# DM1098OAKW_Connector.net
KiCad netlist of a schematic drawn in Altium Designer
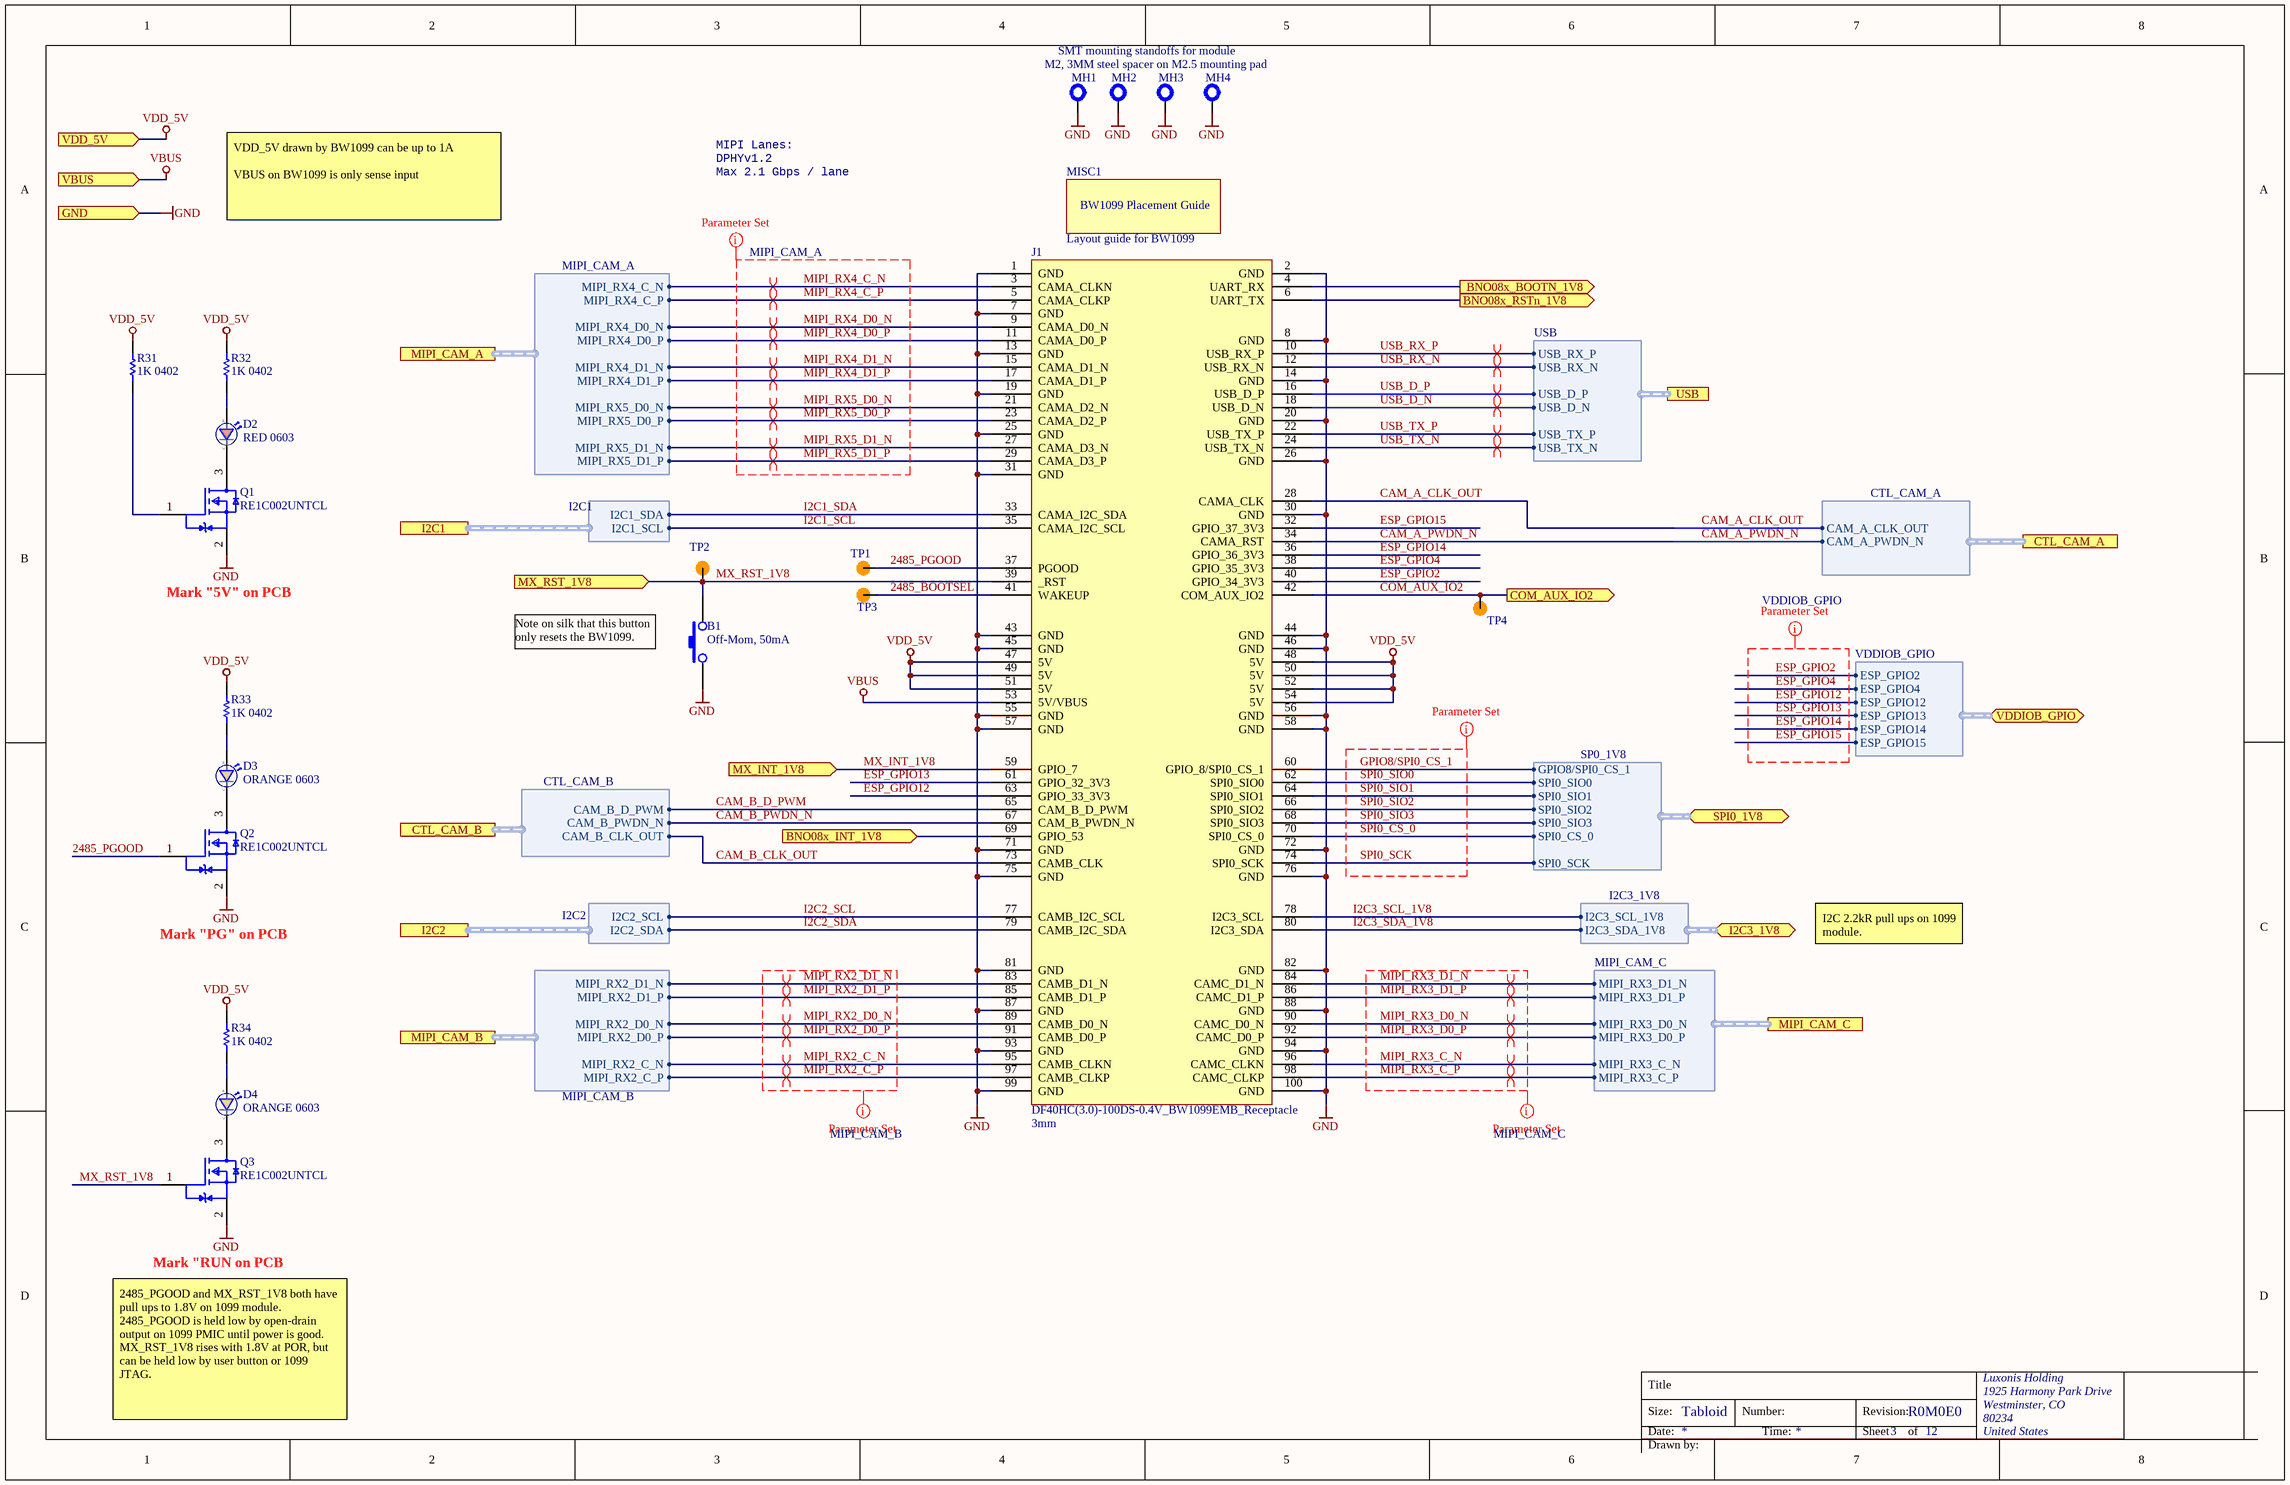
[diagram p0: DM1098OAKW_Connector.SchDoc]

(export (version "E")
  (design (tool "Eeschema 10.0.6"))
  (components
    (comp (ref "B1")
      (value "Off-Mom, 50mA")
      (footprint "LuxonisMaster:DTSM-32N-V")
      (description "SWITCH TACTILE SMT 3.5mm * 6mm , brown 160gf")
      (libsource (lib "LuxonisMaster") (part "DTSM-32N-V"))
    )
    (comp (ref "D2")
      (value "RED 0603")
      (footprint "LuxonisMaster:SML_D1xx8W")
      (description "LED RED DIFFUSED 0603 SMD Red 620nm LED Indication - Discrete 2.2V 0603 (1608 Metric)")
      (libsource (lib "LuxonisMaster") (part "SML-D12U8WT86"))
    )
    (comp (ref "D3")
      (value "ORANGE 0603")
      (footprint "LuxonisMaster:SML_D1xx8W")
      (description "LED ORANGE DIFFUSED 0603 SMD Orange 605nm LED Indication - Discrete 2.2V 0603 (1608 Metric)")
      (libsource (lib "LuxonisMaster") (part "SML-D12D8WT86"))
    )
    (comp (ref "D4")
      (value "ORANGE 0603")
      (footprint "LuxonisMaster:SML_D1xx8W")
      (description "LED ORANGE DIFFUSED 0603 SMD Orange 605nm LED Indication - Discrete 2.2V 0603 (1608 Metric)")
      (libsource (lib "LuxonisMaster") (part "SML-D12D8WT86"))
    )
    (comp (ref "J1")
      (value "DF40HC(3.0)-100DS-0.4V_BW1099EMB_Receptacle")
      (footprint "LuxonisMaster:DF40HC-3.0-100DS-0.4V_minpad")
      (description "CONN RCPT 100POS 0.4MM SMD GOLD EMB PINOUT")
      (fields (field (name "MATED STACKING HEIGHT") "3mm"))
      (libsource (lib "BW1098EMB_R0M0E0") (part "DF40HC(3.0)-100DS-0.4V_BW1099EMB"))
    )
    (comp (ref "MH1")
      (value "M2, 3MM steel spacer on M2.5 mounting pad")
      (footprint "LuxonisMaster:9774030243R")
      (description "MP ROUND STANDOFF M2X0.4 STEEL 3MM")
      (libsource (lib "LuxonisMaster") (part "9774030243R"))
    )
    (comp (ref "MH2")
      (value "M2, 3MM steel spacer on M2.5 mounting pad")
      (footprint "LuxonisMaster:9774030243R")
      (description "MP ROUND STANDOFF M2X0.4 STEEL 3MM")
      (libsource (lib "LuxonisMaster") (part "9774030243R"))
    )
    (comp (ref "MH3")
      (value "M2, 3MM steel spacer on M2.5 mounting pad")
      (footprint "LuxonisMaster:9774030243R")
      (description "MP ROUND STANDOFF M2X0.4 STEEL 3MM")
      (libsource (lib "LuxonisMaster") (part "9774030243R"))
    )
    (comp (ref "MH4")
      (value "M2, 3MM steel spacer on M2.5 mounting pad")
      (footprint "LuxonisMaster:9774030243R")
      (description "MP ROUND STANDOFF M2X0.4 STEEL 3MM")
      (libsource (lib "LuxonisMaster") (part "9774030243R"))
    )
    (comp (ref "MISC1")
      (value "Layout guide for BW1099")
      (footprint "BW1099_R3_KTHSNF_Footprint")
      (description "MISC - Use for aligning BW1099 mount")
      (libsource (lib "LuxonisMaster") (part "BW1099_Footprint"))
    )
    (comp (ref "Q1")
      (value "RE1C002UNTCL")
      (footprint "LuxonisMaster:RE1C002UNTCL")
      (description "MOSFET N-CH 20V 0.2A EMT3")
      (libsource (lib "LuxonisMaster") (part "RE1C002UNTCL"))
    )
    (comp (ref "Q2")
      (value "RE1C002UNTCL")
      (footprint "LuxonisMaster:RE1C002UNTCL")
      (description "MOSFET N-CH 20V 0.2A EMT3")
      (libsource (lib "LuxonisMaster") (part "RE1C002UNTCL"))
    )
    (comp (ref "Q3")
      (value "RE1C002UNTCL")
      (footprint "LuxonisMaster:RE1C002UNTCL")
      (description "MOSFET N-CH 20V 0.2A EMT3")
      (libsource (lib "LuxonisMaster") (part "RE1C002UNTCL"))
    )
    (comp (ref "R31")
      (value "1K 0402")
      (footprint "RES_Altium_Vault_Generic:RESC0402(1005)_L")
      (fields (field (name "TOLERANCE") "1%"))
      (libsource (lib "LuxonisMaster") (part "RC0402FR-071KL"))
    )
    (comp (ref "R32")
      (value "1K 0402")
      (footprint "RES_Altium_Vault_Generic:RESC0402(1005)_L")
      (fields (field (name "TOLERANCE") "1%"))
      (libsource (lib "LuxonisMaster") (part "RC0402FR-071KL"))
    )
    (comp (ref "R33")
      (value "1K 0402")
      (footprint "RES_Altium_Vault_Generic:RESC0402(1005)_L")
      (fields (field (name "TOLERANCE") "1%"))
      (libsource (lib "LuxonisMaster") (part "RC0402FR-071KL"))
    )
    (comp (ref "R34")
      (value "1K 0402")
      (footprint "RES_Altium_Vault_Generic:RESC0402(1005)_L")
      (fields (field (name "TOLERANCE") "1%"))
      (libsource (lib "LuxonisMaster") (part "RC0402FR-071KL"))
    )
    (comp (ref "TP1")
      (value "TP100_200_NS")
      (footprint "LuxonisMaster:TP100_200_NS")
      (libsource (lib "LuxonisMaster") (part "TEST_POINT"))
    )
    (comp (ref "TP2")
      (value "TP100_200_NS")
      (footprint "LuxonisMaster:TP100_200_NS")
      (libsource (lib "LuxonisMaster") (part "TEST_POINT"))
    )
    (comp (ref "TP3")
      (value "TP100_200_NS")
      (footprint "LuxonisMaster:TP100_200_NS")
      (libsource (lib "LuxonisMaster") (part "TEST_POINT"))
    )
    (comp (ref "TP4")
      (value "TP100_200_NS")
      (footprint "LuxonisMaster:TP100_200_NS")
      (libsource (lib "LuxonisMaster") (part "TEST_POINT"))
    )
  )
  (nets
    (net (code "12") (name "/2485_BOOTSEL") (class "Default")
      (node (ref "J1") (pin "41") (pinfunction "WAKEUP_41") (pintype "passive"))
      (node (ref "TP3") (pin "1") (pintype "passive"))
    )
    (net (code "13") (name "/2485_PGOOD") (class "Default")
      (node (ref "J1") (pin "37") (pinfunction "PGOOD_37") (pintype "passive"))
      (node (ref "Q2") (pin "1") (pinfunction "Gate_1") (pintype "passive"))
      (node (ref "TP1") (pin "1") (pintype "passive"))
    )
    (net (code "14") (name "/BNO08x_BOOTN_1V8") (class "Default")
      (node (ref "J1") (pin "4") (pinfunction "UART_RX_4") (pintype "passive"))
    )
    (net (code "15") (name "/BNO08x_INT_1V8") (class "Default")
      (node (ref "J1") (pin "69") (pinfunction "GPIO_53_69") (pintype "passive"))
    )
    (net (code "16") (name "/BNO08x_RSTn_1V8") (class "Default")
      (node (ref "J1") (pin "6") (pinfunction "UART_TX_6") (pintype "passive"))
    )
    (net (code "17") (name "/CAM_A_CLK_OUT") (class "Default")
      (node (ref "J1") (pin "28") (pinfunction "CAMA_CLK_28") (pintype "passive"))
    )
    (net (code "18") (name "/CAM_A_PWDN_N") (class "Default")
      (node (ref "J1") (pin "34") (pinfunction "CAMA_RST_34") (pintype "passive"))
    )
    (net (code "19") (name "/CAM_B_CLK_OUT") (class "Default")
      (node (ref "J1") (pin "73") (pinfunction "CAMB_CLK_73") (pintype "passive"))
    )
    (net (code "20") (name "/CAM_B_D_PWM") (class "Default")
      (node (ref "J1") (pin "65") (pinfunction "CAM_B_D_PWM_65") (pintype "passive"))
    )
    (net (code "21") (name "/CAM_B_PWDN_N") (class "Default")
      (node (ref "J1") (pin "67") (pinfunction "CAM_B_PWDN_N_67") (pintype "passive"))
    )
    (net (code "22") (name "/COM_AUX_IO2") (class "Default")
      (node (ref "J1") (pin "42") (pinfunction "COM_AUX_IO2_42") (pintype "passive"))
      (node (ref "TP4") (pin "1") (pintype "passive"))
    )
    (net (code "23") (name "/ESP_GPIO2") (class "Default")
      (node (ref "J1") (pin "40") (pinfunction "GPIO_34_3V3_40") (pintype "passive"))
    )
    (net (code "24") (name "/ESP_GPIO4") (class "Default")
      (node (ref "J1") (pin "38") (pinfunction "GPIO_35_3V3_38") (pintype "passive"))
    )
    (net (code "25") (name "/ESP_GPIO12") (class "Default")
      (node (ref "J1") (pin "63") (pinfunction "GPIO_33_3V3_63") (pintype "passive"))
    )
    (net (code "26") (name "/ESP_GPIO13") (class "Default")
      (node (ref "J1") (pin "61") (pinfunction "GPIO_32_3V3_61") (pintype "passive"))
    )
    (net (code "27") (name "/ESP_GPIO14") (class "Default")
      (node (ref "J1") (pin "36") (pinfunction "GPIO_36_3V3_36") (pintype "passive"))
    )
    (net (code "28") (name "/ESP_GPIO15") (class "Default")
      (node (ref "J1") (pin "32") (pinfunction "GPIO_37_3V3_32") (pintype "passive"))
    )
    (net (code "29") (name "/GPIO8{slash}SPI0_CS_1") (class "Default")
      (node (ref "J1") (pin "60") (pinfunction "GPIO_8/SPI0_CS_1_60") (pintype "passive"))
    )
    (net (code "30") (name "/I2C1_SCL") (class "Default")
      (node (ref "J1") (pin "35") (pinfunction "CAMA_I2C_SCL_35") (pintype "passive"))
    )
    (net (code "31") (name "/I2C1_SDA") (class "Default")
      (node (ref "J1") (pin "33") (pinfunction "CAMA_I2C_SDA_33") (pintype "passive"))
    )
    (net (code "32") (name "/I2C2_SCL") (class "Default")
      (node (ref "J1") (pin "77") (pinfunction "CAMB_I2C_SCL_77") (pintype "passive"))
    )
    (net (code "33") (name "/I2C2_SDA") (class "Default")
      (node (ref "J1") (pin "79") (pinfunction "CAMB_I2C_SDA_79") (pintype "passive"))
    )
    (net (code "34") (name "/I2C3_SCL_1V8") (class "Default")
      (node (ref "J1") (pin "78") (pinfunction "I2C3_SCL_78") (pintype "passive"))
    )
    (net (code "35") (name "/I2C3_SDA_1V8") (class "Default")
      (node (ref "J1") (pin "80") (pinfunction "I2C3_SDA_80") (pintype "passive"))
    )
    (net (code "36") (name "/MIPI_RX2_C_N") (class "Default")
      (node (ref "J1") (pin "95") (pinfunction "CAMB_CLKN_95") (pintype "passive"))
    )
    (net (code "37") (name "/MIPI_RX2_C_P") (class "Default")
      (node (ref "J1") (pin "97") (pinfunction "CAMB_CLKP_97") (pintype "passive"))
    )
    (net (code "38") (name "/MIPI_RX2_D0_N") (class "Default")
      (node (ref "J1") (pin "89") (pinfunction "CAMB_D0_N_89") (pintype "passive"))
    )
    (net (code "39") (name "/MIPI_RX2_D0_P") (class "Default")
      (node (ref "J1") (pin "91") (pinfunction "CAMB_D0_P_91") (pintype "passive"))
    )
    (net (code "40") (name "/MIPI_RX2_D1_N") (class "Default")
      (node (ref "J1") (pin "83") (pinfunction "CAMB_D1_N_83") (pintype "passive"))
    )
    (net (code "41") (name "/MIPI_RX2_D1_P") (class "Default")
      (node (ref "J1") (pin "85") (pinfunction "CAMB_D1_P_85") (pintype "passive"))
    )
    (net (code "42") (name "/MIPI_RX3_C_N") (class "Default")
      (node (ref "J1") (pin "96") (pinfunction "CAMC_CLKN_96") (pintype "passive"))
    )
    (net (code "43") (name "/MIPI_RX3_C_P") (class "Default")
      (node (ref "J1") (pin "98") (pinfunction "CAMC_CLKP_98") (pintype "passive"))
    )
    (net (code "44") (name "/MIPI_RX3_D0_N") (class "Default")
      (node (ref "J1") (pin "90") (pinfunction "CAMC_D0_N_90") (pintype "passive"))
    )
    (net (code "45") (name "/MIPI_RX3_D0_P") (class "Default")
      (node (ref "J1") (pin "92") (pinfunction "CAMC_D0_P_92") (pintype "passive"))
    )
    (net (code "46") (name "/MIPI_RX3_D1_N") (class "Default")
      (node (ref "J1") (pin "84") (pinfunction "CAMC_D1_N_84") (pintype "passive"))
    )
    (net (code "47") (name "/MIPI_RX3_D1_P") (class "Default")
      (node (ref "J1") (pin "86") (pinfunction "CAMC_D1_P_86") (pintype "passive"))
    )
    (net (code "48") (name "/MIPI_RX4_C_N") (class "Default")
      (node (ref "J1") (pin "3") (pinfunction "CAMA_CLKN_3") (pintype "passive"))
    )
    (net (code "49") (name "/MIPI_RX4_C_P") (class "Default")
      (node (ref "J1") (pin "5") (pinfunction "CAMA_CLKP_5") (pintype "passive"))
    )
    (net (code "50") (name "/MIPI_RX4_D0_N") (class "Default")
      (node (ref "J1") (pin "9") (pinfunction "CAMA_D0_N_9") (pintype "passive"))
    )
    (net (code "51") (name "/MIPI_RX4_D0_P") (class "Default")
      (node (ref "J1") (pin "11") (pinfunction "CAMA_D0_P_11") (pintype "passive"))
    )
    (net (code "52") (name "/MIPI_RX4_D1_N") (class "Default")
      (node (ref "J1") (pin "15") (pinfunction "CAMA_D1_N_15") (pintype "passive"))
    )
    (net (code "53") (name "/MIPI_RX4_D1_P") (class "Default")
      (node (ref "J1") (pin "17") (pinfunction "CAMA_D1_P_17") (pintype "passive"))
    )
    (net (code "54") (name "/MIPI_RX5_D0_N") (class "Default")
      (node (ref "J1") (pin "21") (pinfunction "CAMA_D2_N_21") (pintype "passive"))
    )
    (net (code "55") (name "/MIPI_RX5_D0_P") (class "Default")
      (node (ref "J1") (pin "23") (pinfunction "CAMA_D2_P_23") (pintype "passive"))
    )
    (net (code "56") (name "/MIPI_RX5_D1_N") (class "Default")
      (node (ref "J1") (pin "27") (pinfunction "CAMA_D3_N_27") (pintype "passive"))
    )
    (net (code "57") (name "/MIPI_RX5_D1_P") (class "Default")
      (node (ref "J1") (pin "29") (pinfunction "CAMA_D3_P_29") (pintype "passive"))
    )
    (net (code "58") (name "/MX_INT_1V8") (class "Default")
      (node (ref "J1") (pin "59") (pinfunction "GPIO_7_59") (pintype "passive"))
    )
    (net (code "59") (name "/MX_RST_1V8") (class "Default")
      (node (ref "B1") (pin "2") (pinfunction "2_2") (pintype "passive"))
      (node (ref "J1") (pin "39") (pinfunction "_RST_39") (pintype "passive"))
      (node (ref "Q3") (pin "1") (pinfunction "Gate_1") (pintype "passive"))
      (node (ref "TP2") (pin "1") (pintype "passive"))
    )
    (net (code "60") (name "/SPI0_CS_0") (class "Default")
      (node (ref "J1") (pin "70") (pinfunction "SPI0_CS_0_70") (pintype "passive"))
    )
    (net (code "61") (name "/SPI0_SCK") (class "Default")
      (node (ref "J1") (pin "74") (pinfunction "SPI0_SCK_74") (pintype "passive"))
    )
    (net (code "62") (name "/SPI0_SIO0") (class "Default")
      (node (ref "J1") (pin "62") (pinfunction "SPI0_SIO0_62") (pintype "passive"))
    )
    (net (code "63") (name "/SPI0_SIO1") (class "Default")
      (node (ref "J1") (pin "64") (pinfunction "SPI0_SIO1_64") (pintype "passive"))
    )
    (net (code "64") (name "/SPI0_SIO2") (class "Default")
      (node (ref "J1") (pin "66") (pinfunction "SPI0_SIO2_66") (pintype "passive"))
    )
    (net (code "65") (name "/SPI0_SIO3") (class "Default")
      (node (ref "J1") (pin "68") (pinfunction "SPI0_SIO3_68") (pintype "passive"))
    )
    (net (code "66") (name "/USB_D_N") (class "Default")
      (node (ref "J1") (pin "18") (pinfunction "USB_D_N_18") (pintype "passive"))
    )
    (net (code "67") (name "/USB_D_P") (class "Default")
      (node (ref "J1") (pin "16") (pinfunction "USB_D_P_16") (pintype "passive"))
    )
    (net (code "68") (name "/USB_RX_N") (class "Default")
      (node (ref "J1") (pin "12") (pinfunction "USB_RX_N_12") (pintype "passive"))
    )
    (net (code "69") (name "/USB_RX_P") (class "Default")
      (node (ref "J1") (pin "10") (pinfunction "USB_RX_P_10") (pintype "passive"))
    )
    (net (code "70") (name "/USB_TX_N") (class "Default")
      (node (ref "J1") (pin "24") (pinfunction "USB_TX_N_24") (pintype "passive"))
    )
    (net (code "71") (name "/USB_TX_P") (class "Default")
      (node (ref "J1") (pin "22") (pinfunction "USB_TX_P_22") (pintype "passive"))
    )
    (net (code "83") (name "GND") (class "Default")
      (node (ref "B1") (pin "1") (pinfunction "1_1") (pintype "passive"))
      (node (ref "J1") (pin "1") (pinfunction "GND_1") (pintype "passive"))
      (node (ref "J1") (pin "100") (pinfunction "GND_100") (pintype "passive"))
      (node (ref "J1") (pin "13") (pinfunction "GND_13") (pintype "passive"))
      (node (ref "J1") (pin "14") (pinfunction "GND_14") (pintype "passive"))
      (node (ref "J1") (pin "19") (pinfunction "GND_19") (pintype "passive"))
      (node (ref "J1") (pin "2") (pinfunction "GND_2") (pintype "passive"))
      (node (ref "J1") (pin "20") (pinfunction "GND_20") (pintype "passive"))
      (node (ref "J1") (pin "25") (pinfunction "GND_25") (pintype "passive"))
      (node (ref "J1") (pin "26") (pinfunction "GND_26") (pintype "passive"))
      (node (ref "J1") (pin "30") (pinfunction "GND_30") (pintype "passive"))
      (node (ref "J1") (pin "31") (pinfunction "GND_31") (pintype "passive"))
      (node (ref "J1") (pin "43") (pinfunction "GND_43") (pintype "passive"))
      (node (ref "J1") (pin "44") (pinfunction "GND_44") (pintype "passive"))
      (node (ref "J1") (pin "45") (pinfunction "GND_45") (pintype "passive"))
      (node (ref "J1") (pin "46") (pinfunction "GND_46") (pintype "passive"))
      (node (ref "J1") (pin "55") (pinfunction "GND_55") (pintype "passive"))
      (node (ref "J1") (pin "56") (pinfunction "GND_56") (pintype "passive"))
      (node (ref "J1") (pin "57") (pinfunction "GND_57") (pintype "passive"))
      (node (ref "J1") (pin "58") (pinfunction "GND_58") (pintype "passive"))
      (node (ref "J1") (pin "7") (pinfunction "GND_7") (pintype "passive"))
      (node (ref "J1") (pin "71") (pinfunction "GND_71") (pintype "passive"))
      (node (ref "J1") (pin "72") (pinfunction "GND_72") (pintype "passive"))
      (node (ref "J1") (pin "75") (pinfunction "GND_75") (pintype "passive"))
      (node (ref "J1") (pin "76") (pinfunction "GND_76") (pintype "passive"))
      (node (ref "J1") (pin "8") (pinfunction "GND_8") (pintype "passive"))
      (node (ref "J1") (pin "81") (pinfunction "GND_81") (pintype "passive"))
      (node (ref "J1") (pin "82") (pinfunction "GND_82") (pintype "passive"))
      (node (ref "J1") (pin "87") (pinfunction "GND_87") (pintype "passive"))
      (node (ref "J1") (pin "88") (pinfunction "GND_88") (pintype "passive"))
      (node (ref "J1") (pin "93") (pinfunction "GND_93") (pintype "passive"))
      (node (ref "J1") (pin "94") (pinfunction "GND_94") (pintype "passive"))
      (node (ref "J1") (pin "99") (pinfunction "GND_99") (pintype "passive"))
      (node (ref "MH1") (pin "1") (pintype "passive"))
      (node (ref "MH2") (pin "1") (pintype "passive"))
      (node (ref "MH3") (pin "1") (pintype "passive"))
      (node (ref "MH4") (pin "1") (pintype "passive"))
      (node (ref "Q1") (pin "2") (pinfunction "Source_2") (pintype "passive"))
      (node (ref "Q2") (pin "2") (pinfunction "Source_2") (pintype "passive"))
      (node (ref "Q3") (pin "2") (pinfunction "Source_2") (pintype "passive"))
    )
    (net (code "84") (name "Net-(D2-A)") (class "Default")
      (node (ref "D2") (pin "2") (pinfunction "A_2") (pintype "passive"))
      (node (ref "R32") (pin "1") (pinfunction "1_1") (pintype "passive"))
    )
    (net (code "85") (name "Net-(D2-C)") (class "Default")
      (node (ref "D2") (pin "1") (pinfunction "C_1") (pintype "passive"))
      (node (ref "Q1") (pin "3") (pinfunction "Drain_3") (pintype "passive"))
    )
    (net (code "86") (name "Net-(D3-A)") (class "Default")
      (node (ref "D3") (pin "2") (pinfunction "A_2") (pintype "passive"))
      (node (ref "R33") (pin "1") (pinfunction "1_1") (pintype "passive"))
    )
    (net (code "87") (name "Net-(D3-C)") (class "Default")
      (node (ref "D3") (pin "1") (pinfunction "C_1") (pintype "passive"))
      (node (ref "Q2") (pin "3") (pinfunction "Drain_3") (pintype "passive"))
    )
    (net (code "88") (name "Net-(D4-A)") (class "Default")
      (node (ref "D4") (pin "2") (pinfunction "A_2") (pintype "passive"))
      (node (ref "R34") (pin "1") (pinfunction "1_1") (pintype "passive"))
    )
    (net (code "89") (name "Net-(D4-C)") (class "Default")
      (node (ref "D4") (pin "1") (pinfunction "C_1") (pintype "passive"))
      (node (ref "Q3") (pin "3") (pinfunction "Drain_3") (pintype "passive"))
    )
    (net (code "90") (name "Net-(Q1-Gate)") (class "Default")
      (node (ref "Q1") (pin "1") (pinfunction "Gate_1") (pintype "passive"))
      (node (ref "R31") (pin "1") (pinfunction "1_1") (pintype "passive"))
    )
    (net (code "91") (name "VBUS") (class "Default")
      (node (ref "J1") (pin "53") (pinfunction "5V/VBUS_53") (pintype "passive"))
    )
    (net (code "92") (name "VDD_5V") (class "Default")
      (node (ref "J1") (pin "47") (pinfunction "5V_47") (pintype "passive"))
      (node (ref "J1") (pin "48") (pinfunction "5V_48") (pintype "passive"))
      (node (ref "J1") (pin "49") (pinfunction "5V_49") (pintype "passive"))
      (node (ref "J1") (pin "50") (pinfunction "5V_50") (pintype "passive"))
      (node (ref "J1") (pin "51") (pinfunction "5V_51") (pintype "passive"))
      (node (ref "J1") (pin "52") (pinfunction "5V_52") (pintype "passive"))
      (node (ref "J1") (pin "54") (pinfunction "5V_54") (pintype "passive"))
      (node (ref "R31") (pin "2") (pinfunction "2_2") (pintype "passive"))
      (node (ref "R32") (pin "2") (pinfunction "2_2") (pintype "passive"))
      (node (ref "R33") (pin "2") (pinfunction "2_2") (pintype "passive"))
      (node (ref "R34") (pin "2") (pinfunction "2_2") (pintype "passive"))
    )
  )
)
